# tnb_mns_slave.net
KiCad netlist of a schematic drawn in Altium Designer
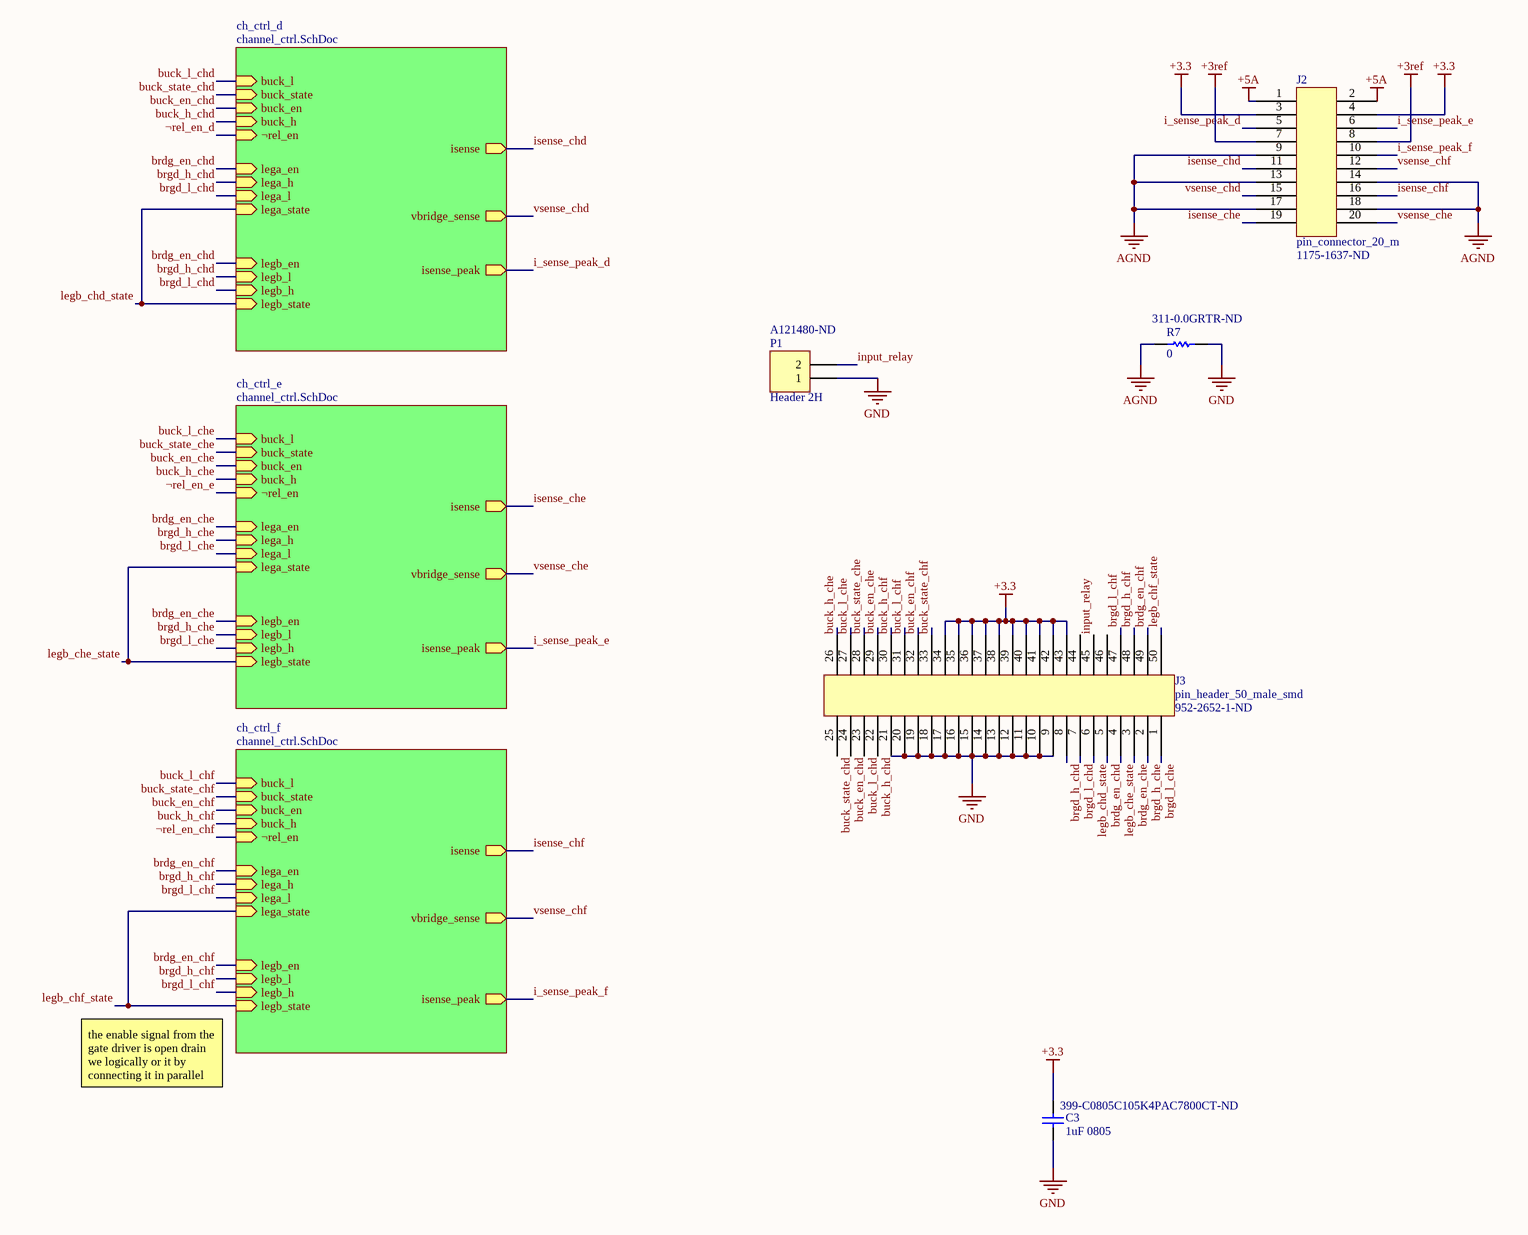
[diagram p0: tnb_mns_slave.SchDoc]

(export (version "E")
  (design (tool "Eeschema 10.0.6"))
  (components
    (comp (ref "C3")
      (value "1uF 0805")
      (footprint "Model Name")
      (description "Capacitor")
      (fields
        (field (name "SUPPLIER PART NUMBER 1") "399-C0805C105K4PAC7800CT-ND")
        (field (name "PUBLISHER") "Altium Limited")
      )
      (libsource (lib "Miscellaneous Devices") (part "Cap"))
    )
    (comp (ref "J2")
      (value "pin_connector_20_m")
      (footprint "PIN_20_MALE_3220-20-0300-00")
      (fields (field (name "SUPPLIER PART NUMBER 1") "1175-1637-ND"))
      (libsource (lib "coil_driver_lib") (part "pin_connector_20_m"))
    )
    (comp (ref "J3")
      (value "pin_header_50_male_smd")
      (footprint "pin_connector_50_m_1.27_smd")
      (description "Mating Product : 952-2565-ND")
      (fields (field (name "SUPPLIER PART NUMBER 1") "952-2652-1-ND"))
      (libsource (lib "coil_driver_lib") (part "pin_header_50_male_smd"))
    )
    (comp (ref "P1")
      (value "Header 2H")
      (footprint "HEADER_1_2_f")
      (description "Header, 2-Pin, Right Angle")
      (fields
        (field (name "SUPPLIER PART NUMBER 1") "A121480-ND")
        (field (name "PUBLISHER") "Altium Limited")
      )
      (libsource (lib "Miscellaneous Connectors") (part "Header 2H"))
    )
    (comp (ref "R7")
      (value "0")
      (footprint "RES 0603_1608")
      (description "Resistor")
      (fields
        (field (name "SUPPLIER PART NUMBER 1") "311-0.0GRTR-ND")
        (field (name "PUBLISHER") "Altium Limited")
      )
      (libsource (lib "Miscellaneous Devices") (part "Res1"))
    )
  )
  (nets
    (net (code "1") (name "+3.3") (class "Default")
      (node (ref "C3") (pin "2") (pinfunction "2_2") (pintype "passive"))
      (node (ref "J2") (pin "3") (pintype "passive"))
      (node (ref "J2") (pin "4") (pintype "passive"))
      (node (ref "J3") (pin "34") (pintype "passive"))
      (node (ref "J3") (pin "35") (pintype "passive"))
      (node (ref "J3") (pin "36") (pintype "passive"))
      (node (ref "J3") (pin "37") (pintype "passive"))
      (node (ref "J3") (pin "38") (pintype "passive"))
      (node (ref "J3") (pin "39") (pintype "passive"))
      (node (ref "J3") (pin "40") (pintype "passive"))
      (node (ref "J3") (pin "41") (pintype "passive"))
      (node (ref "J3") (pin "42") (pintype "passive"))
      (node (ref "J3") (pin "43") (pintype "passive"))
    )
    (net (code "2") (name "+3ref") (class "Default")
      (node (ref "J2") (pin "7") (pintype "passive"))
      (node (ref "J2") (pin "8") (pintype "passive"))
    )
    (net (code "3") (name "+5A") (class "Default")
      (node (ref "J2") (pin "1") (pintype "passive"))
      (node (ref "J2") (pin "2") (pintype "passive"))
    )
    (net (code "4") (name "/brdg_en_chd") (class "Default") (node (ref "J3") (pin "5") (pintype "passive")))
    (net (code "5") (name "/brdg_en_che") (class "Default") (node (ref "J3") (pin "3") (pintype "passive")))
    (net (code "6") (name "/brdg_en_chf") (class "Default") (node (ref "J3") (pin "49") (pintype "passive")))
    (net (code "7") (name "/brgd_h_chd") (class "Default") (node (ref "J3") (pin "8") (pintype "passive")))
    (net (code "8") (name "/brgd_h_che") (class "Default") (node (ref "J3") (pin "2") (pintype "passive")))
    (net (code "9") (name "/brgd_h_chf") (class "Default") (node (ref "J3") (pin "48") (pintype "passive")))
    (net (code "10") (name "/brgd_l_chd") (class "Default") (node (ref "J3") (pin "7") (pintype "passive")))
    (net (code "11") (name "/brgd_l_che") (class "Default") (node (ref "J3") (pin "1") (pintype "passive")))
    (net (code "12") (name "/brgd_l_chf") (class "Default") (node (ref "J3") (pin "47") (pintype "passive")))
    (net (code "13") (name "/buck_en_chd") (class "Default") (node (ref "J3") (pin "24") (pintype "passive")))
    (net (code "14") (name "/buck_en_che") (class "Default") (node (ref "J3") (pin "29") (pintype "passive")))
    (net (code "15") (name "/buck_en_chf") (class "Default") (node (ref "J3") (pin "32") (pintype "passive")))
    (net (code "16") (name "/buck_h_chd") (class "Default") (node (ref "J3") (pin "22") (pintype "passive")))
    (net (code "17") (name "/buck_h_che") (class "Default") (node (ref "J3") (pin "26") (pintype "passive")))
    (net (code "18") (name "/buck_h_chf") (class "Default") (node (ref "J3") (pin "30") (pintype "passive")))
    (net (code "19") (name "/buck_l_chd") (class "Default") (node (ref "J3") (pin "23") (pintype "passive")))
    (net (code "20") (name "/buck_l_che") (class "Default") (node (ref "J3") (pin "27") (pintype "passive")))
    (net (code "21") (name "/buck_l_chf") (class "Default") (node (ref "J3") (pin "31") (pintype "passive")))
    (net (code "22") (name "/buck_state_chd") (class "Default")
      (node (ref "J3") (pin "25") (pintype "passive"))
    )
    (net (code "23") (name "/buck_state_che") (class "Default")
      (node (ref "J3") (pin "28") (pintype "passive"))
    )
    (net (code "24") (name "/buck_state_chf") (class "Default")
      (node (ref "J3") (pin "33") (pintype "passive"))
    )
    (net (code "25") (name "/i_sense_peak_d") (class "Default")
      (node (ref "J2") (pin "5") (pintype "passive"))
    )
    (net (code "26") (name "/i_sense_peak_e") (class "Default")
      (node (ref "J2") (pin "6") (pintype "passive"))
    )
    (net (code "27") (name "/i_sense_peak_f") (class "Default")
      (node (ref "J2") (pin "10") (pintype "passive"))
    )
    (net (code "28") (name "/input_relay") (class "Default")
      (node (ref "J3") (pin "45") (pintype "passive"))
      (node (ref "P1") (pin "2") (pinfunction "2_2") (pintype "passive"))
    )
    (net (code "29") (name "/isense_chd") (class "Default") (node (ref "J2") (pin "11") (pintype "passive")))
    (net (code "30") (name "/isense_che") (class "Default") (node (ref "J2") (pin "19") (pintype "passive")))
    (net (code "31") (name "/isense_chf") (class "Default") (node (ref "J2") (pin "16") (pintype "passive")))
    (net (code "32") (name "/legb_chd_state") (class "Default")
      (node (ref "J3") (pin "6") (pintype "passive"))
    )
    (net (code "33") (name "/legb_che_state") (class "Default")
      (node (ref "J3") (pin "4") (pintype "passive"))
    )
    (net (code "34") (name "/legb_chf_state") (class "Default")
      (node (ref "J3") (pin "50") (pintype "passive"))
    )
    (net (code "35") (name "/vsense_chd") (class "Default") (node (ref "J2") (pin "15") (pintype "passive")))
    (net (code "36") (name "/vsense_che") (class "Default") (node (ref "J2") (pin "20") (pintype "passive")))
    (net (code "37") (name "/vsense_chf") (class "Default") (node (ref "J2") (pin "12") (pintype "passive")))
    (net (code "41") (name "AGND") (class "Default")
      (node (ref "J2") (pin "13") (pintype "passive"))
      (node (ref "J2") (pin "14") (pintype "passive"))
      (node (ref "J2") (pin "17") (pintype "passive"))
      (node (ref "J2") (pin "18") (pintype "passive"))
      (node (ref "J2") (pin "9") (pintype "passive"))
      (node (ref "R7") (pin "1") (pinfunction "1_1") (pintype "passive"))
    )
    (net (code "42") (name "GND") (class "Default")
      (node (ref "C3") (pin "1") (pinfunction "1_1") (pintype "passive"))
      (node (ref "J3") (pin "10") (pintype "passive"))
      (node (ref "J3") (pin "11") (pintype "passive"))
      (node (ref "J3") (pin "12") (pintype "passive"))
      (node (ref "J3") (pin "13") (pintype "passive"))
      (node (ref "J3") (pin "14") (pintype "passive"))
      (node (ref "J3") (pin "15") (pintype "passive"))
      (node (ref "J3") (pin "16") (pintype "passive"))
      (node (ref "J3") (pin "17") (pintype "passive"))
      (node (ref "J3") (pin "18") (pintype "passive"))
      (node (ref "J3") (pin "19") (pintype "passive"))
      (node (ref "J3") (pin "20") (pintype "passive"))
      (node (ref "J3") (pin "21") (pintype "passive"))
      (node (ref "J3") (pin "9") (pintype "passive"))
      (node (ref "P1") (pin "1") (pinfunction "1_1") (pintype "passive"))
      (node (ref "R7") (pin "2") (pinfunction "2_2") (pintype "passive"))
    )
    (net (code "43") (name "unconnected-(J3-Pad44)") (class "Default")
      (node (ref "J3") (pin "44") (pintype "passive"))
    )
    (net (code "44") (name "unconnected-(J3-Pad46)") (class "Default")
      (node (ref "J3") (pin "46") (pintype "passive"))
    )
  )
)
